# SolarPanels_Power_Processing.net
KiCad netlist of a schematic drawn in EAGLE
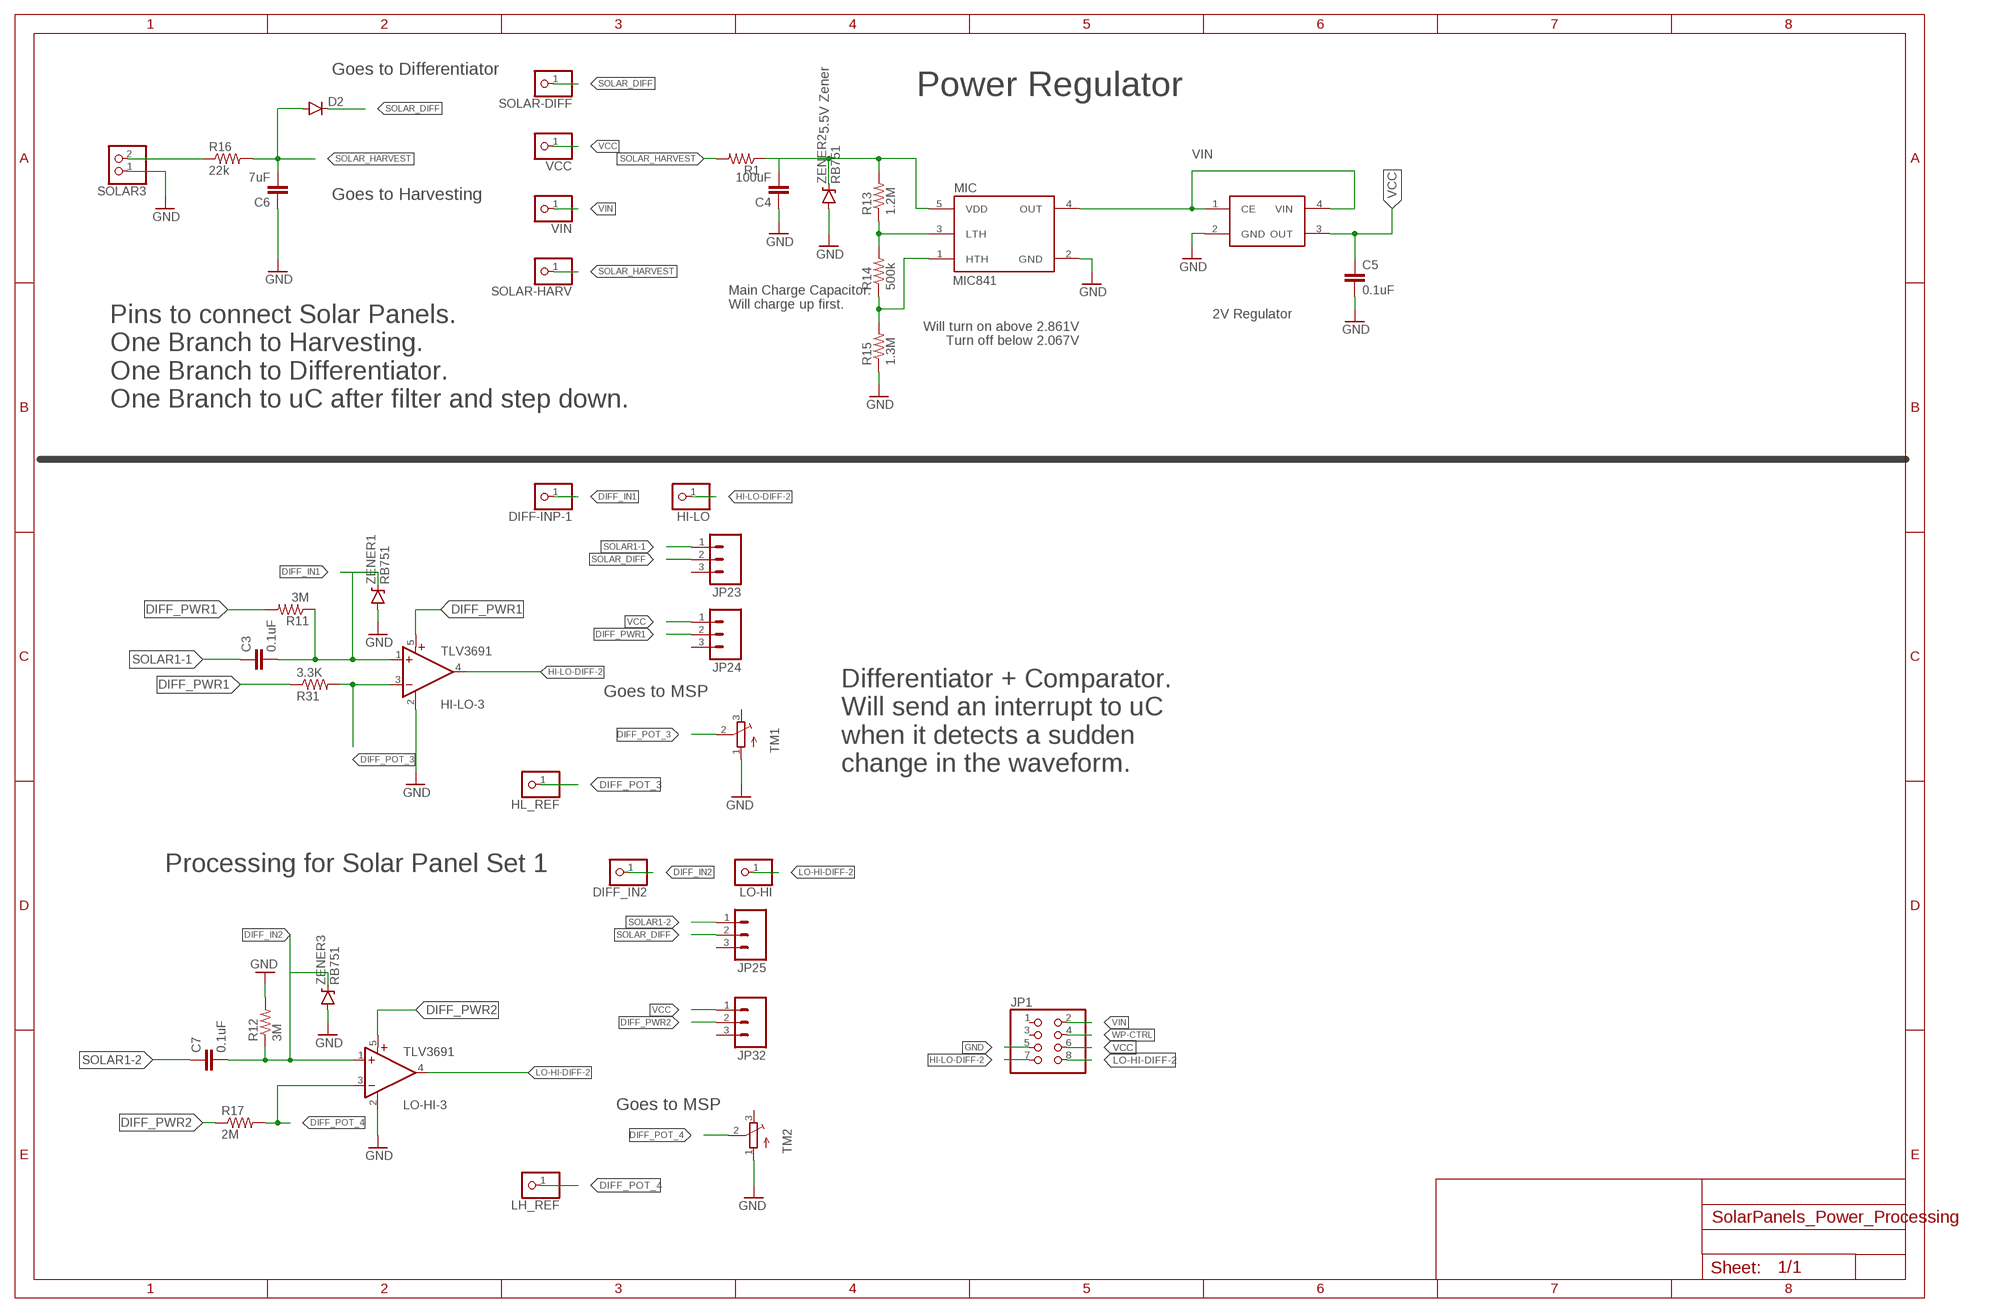
[diagram p0: schematic, sheet 1]

(export (version "E")
  (design (tool "Eeschema 10.0.6"))
  (components
    (comp (ref "3.3K")
      (value "R31")
      (footprint "eagle-import:0805")
      (libsource (lib "eagle-import") (part "RESISTOR0805-RES"))
    )
    (comp (ref "C3")
      (value "0.1uF")
      (footprint "eagle-import:0805")
      (libsource (lib "eagle-import") (part "CAP0805"))
    )
    (comp (ref "C4")
      (value "100uF")
      (footprint "eagle-import:0805")
      (libsource (lib "eagle-import") (part "CAP0805"))
    )
    (comp (ref "C5")
      (value "0.1uF")
      (footprint "eagle-import:0805")
      (libsource (lib "eagle-import") (part "CAP0805"))
    )
    (comp (ref "C6")
      (value "7uF")
      (footprint "eagle-import:0805")
      (libsource (lib "eagle-import") (part "CAP0805"))
    )
    (comp (ref "C7")
      (value "0.1uF")
      (footprint "eagle-import:0805")
      (libsource (lib "eagle-import") (part "CAP0805"))
    )
    (comp (ref "D2")
      (value "DIODESOD523")
      (footprint "eagle-import:SOD523")
      (libsource (lib "eagle-import") (part "DIODESOD523"))
    )
    (comp (ref "DIFF-INP-1")
      (value "PINHD-1X1")
      (footprint "eagle-import:1X01")
      (libsource (lib "eagle-import") (part "PINHD-1X1"))
    )
    (comp (ref "DIFF_IN2")
      (value "PINHD-1X1")
      (footprint "eagle-import:1X01")
      (libsource (lib "eagle-import") (part "PINHD-1X1"))
    )
    (comp (ref "HI-LO")
      (value "PINHD-1X1")
      (footprint "eagle-import:1X01")
      (libsource (lib "eagle-import") (part "PINHD-1X1"))
    )
    (comp (ref "HI-LO-3")
      (value "TLV3691")
      (footprint "eagle-import:SC70-5")
      (libsource (lib "eagle-import") (part "TLV3691"))
    )
    (comp (ref "HL_REF")
      (value "PINHD-1X1")
      (footprint "eagle-import:1X01")
      (libsource (lib "eagle-import") (part "PINHD-1X1"))
    )
    (comp (ref "JP1")
      (value "PINHD-2X4/90")
      (footprint "eagle-import:2X04_90")
      (libsource (lib "eagle-import") (part "PINHD-2X4/90"))
    )
    (comp (ref "JP23")
      (value "M03")
      (footprint "eagle-import:1X03-1.27MM")
      (libsource (lib "eagle-import") (part "M03"))
    )
    (comp (ref "JP24")
      (value "M03")
      (footprint "eagle-import:1X03-1.27MM")
      (libsource (lib "eagle-import") (part "M03"))
    )
    (comp (ref "JP25")
      (value "M03")
      (footprint "eagle-import:1X03-1.27MM")
      (libsource (lib "eagle-import") (part "M03"))
    )
    (comp (ref "JP32")
      (value "M03")
      (footprint "eagle-import:1X03-1.27MM")
      (libsource (lib "eagle-import") (part "M03"))
    )
    (comp (ref "LH_REF")
      (value "PINHD-1X1")
      (footprint "eagle-import:1X01")
      (libsource (lib "eagle-import") (part "PINHD-1X1"))
    )
    (comp (ref "LO-HI")
      (value "PINHD-1X1")
      (footprint "eagle-import:1X01")
      (libsource (lib "eagle-import") (part "PINHD-1X1"))
    )
    (comp (ref "LO-HI-3")
      (value "TLV3691")
      (footprint "eagle-import:SC70-5")
      (libsource (lib "eagle-import") (part "TLV3691"))
    )
    (comp (ref "MIC")
      (value "MIC841")
      (footprint "eagle-import:SC70-5")
      (libsource (lib "eagle-import") (part "MIC841"))
    )
    (comp (ref "NCP")
      (value "NCP583")
      (footprint "eagle-import:SC82-AB_1PRIMARY")
      (libsource (lib "eagle-import") (part "NCP583"))
    )
    (comp (ref "R1")
      (value "RESISTOR0805-RES")
      (footprint "eagle-import:0805")
      (libsource (lib "eagle-import") (part "RESISTOR0805-RES"))
    )
    (comp (ref "R11")
      (value "3M")
      (footprint "eagle-import:0805")
      (libsource (lib "eagle-import") (part "RESISTOR0805-RES"))
    )
    (comp (ref "R12")
      (value "3M")
      (footprint "eagle-import:0805")
      (libsource (lib "eagle-import") (part "RESISTOR0805-RES"))
    )
    (comp (ref "R13")
      (value "1.2M")
      (footprint "eagle-import:0805")
      (libsource (lib "eagle-import") (part "RESISTOR0805-RES"))
    )
    (comp (ref "R14")
      (value "500k")
      (footprint "eagle-import:0805")
      (libsource (lib "eagle-import") (part "RESISTOR0805-RES"))
    )
    (comp (ref "R15")
      (value "1.3M")
      (footprint "eagle-import:0805")
      (libsource (lib "eagle-import") (part "RESISTOR0805-RES"))
    )
    (comp (ref "R16")
      (value "22k")
      (footprint "eagle-import:0805")
      (libsource (lib "eagle-import") (part "RESISTOR0805-RES"))
    )
    (comp (ref "R17")
      (value "2M")
      (footprint "eagle-import:0805")
      (libsource (lib "eagle-import") (part "RESISTOR0805-RES"))
    )
    (comp (ref "SOLAR-DIFF")
      (value "PINHD-1X1")
      (footprint "eagle-import:1X01")
      (libsource (lib "eagle-import") (part "PINHD-1X1"))
    )
    (comp (ref "SOLAR-HARV")
      (value "PINHD-1X1")
      (footprint "eagle-import:1X01")
      (libsource (lib "eagle-import") (part "PINHD-1X1"))
    )
    (comp (ref "SOLAR3")
      (value "PINHD-1X2")
      (footprint "eagle-import:1X02")
      (libsource (lib "eagle-import") (part "PINHD-1X2"))
    )
    (comp (ref "TM1")
      (value "TRIMPOTTC33X")
      (footprint "eagle-import:TC33X")
      (libsource (lib "eagle-import") (part "TRIMPOTTC33X"))
    )
    (comp (ref "TM2")
      (value "TRIMPOTTC33X")
      (footprint "eagle-import:TC33X")
      (libsource (lib "eagle-import") (part "TRIMPOTTC33X"))
    )
    (comp (ref "VCC")
      (value "PINHD-1X1")
      (footprint "eagle-import:1X01")
      (libsource (lib "eagle-import") (part "PINHD-1X1"))
    )
    (comp (ref "VIN")
      (value "PINHD-1X1")
      (footprint "eagle-import:1X01")
      (libsource (lib "eagle-import") (part "PINHD-1X1"))
    )
    (comp (ref "ZENER1")
      (value "RB751")
      (footprint "eagle-import:SOD-523")
      (libsource (lib "eagle-import") (part "DIODE-ZENER"))
    )
    (comp (ref "ZENER2")
      (value "RB751")
      (footprint "eagle-import:SOD-523")
      (libsource (lib "eagle-import") (part "DIODE-ZENER"))
    )
    (comp (ref "ZENER3")
      (value "RB751")
      (footprint "eagle-import:SOD-523")
      (libsource (lib "eagle-import") (part "DIODE-ZENER"))
    )
  )
  (nets
    (net (code "1") (name "DIFF_IN1") (class "Default")
      (node (ref "C3") (pin "2") (pinfunction "2_2") (pintype "passive"))
      (node (ref "DIFF-INP-1") (pin "1") (pinfunction "1_1") (pintype "passive"))
      (node (ref "HI-LO-3") (pin "1") (pinfunction "+IN_1") (pintype "input"))
      (node (ref "R11") (pin "1") (pinfunction "1_1") (pintype "passive"))
      (node (ref "ZENER1") (pin "CATHODE") (pinfunction "C_CATHODE") (pintype "passive"))
    )
    (net (code "2") (name "DIFF_IN2") (class "Default")
      (node (ref "C7") (pin "2") (pinfunction "2_2") (pintype "passive"))
      (node (ref "DIFF_IN2") (pin "1") (pinfunction "1_1") (pintype "passive"))
      (node (ref "LO-HI-3") (pin "1") (pinfunction "+IN_1") (pintype "input"))
      (node (ref "R12") (pin "1") (pinfunction "1_1") (pintype "passive"))
      (node (ref "ZENER3") (pin "CATHODE") (pinfunction "C_CATHODE") (pintype "passive"))
    )
    (net (code "3") (name "DIFF_POT_3") (class "Default")
      (node (ref "3.3K") (pin "2") (pinfunction "2_2") (pintype "passive"))
      (node (ref "HI-LO-3") (pin "3") (pinfunction "-IN_3") (pintype "input"))
      (node (ref "HL_REF") (pin "1") (pinfunction "1_1") (pintype "passive"))
      (node (ref "TM1") (pin "2") (pinfunction "S_2") (pintype "passive"))
    )
    (net (code "4") (name "DIFF_POT_4") (class "Default")
      (node (ref "LH_REF") (pin "1") (pinfunction "1_1") (pintype "passive"))
      (node (ref "LO-HI-3") (pin "3") (pinfunction "-IN_3") (pintype "input"))
      (node (ref "R17") (pin "2") (pinfunction "2_2") (pintype "passive"))
      (node (ref "TM2") (pin "2") (pinfunction "S_2") (pintype "passive"))
    )
    (net (code "5") (name "DIFF_PWR1") (class "Default")
      (node (ref "3.3K") (pin "1") (pinfunction "1_1") (pintype "passive"))
      (node (ref "HI-LO-3") (pin "5") (pinfunction "V+_5") (pintype "power_in"))
      (node (ref "JP24") (pin "2") (pinfunction "2_2") (pintype "passive"))
      (node (ref "R11") (pin "2") (pinfunction "2_2") (pintype "passive"))
    )
    (net (code "6") (name "DIFF_PWR2") (class "Default")
      (node (ref "JP32") (pin "2") (pinfunction "2_2") (pintype "passive"))
      (node (ref "LO-HI-3") (pin "5") (pinfunction "V+_5") (pintype "power_in"))
      (node (ref "R17") (pin "1") (pinfunction "1_1") (pintype "passive"))
    )
    (net (code "7") (name "GND") (class "Default")
      (node (ref "C4") (pin "1") (pinfunction "1_1") (pintype "passive"))
      (node (ref "C5") (pin "2") (pinfunction "2_2") (pintype "passive"))
      (node (ref "C6") (pin "1") (pinfunction "1_1") (pintype "passive"))
      (node (ref "HI-LO-3") (pin "2") (pinfunction "GND_2") (pintype "power_in"))
      (node (ref "JP1") (pin "5") (pinfunction "5_5") (pintype "passive"))
      (node (ref "LO-HI-3") (pin "2") (pinfunction "GND_2") (pintype "power_in"))
      (node (ref "MIC") (pin "2") (pinfunction "GND_2") (pintype "bidirectional"))
      (node (ref "NCP") (pin "2") (pinfunction "GND_2") (pintype "bidirectional"))
      (node (ref "R12") (pin "2") (pinfunction "2_2") (pintype "passive"))
      (node (ref "R15") (pin "1") (pinfunction "1_1") (pintype "passive"))
      (node (ref "SOLAR3") (pin "1") (pinfunction "1_1") (pintype "passive"))
      (node (ref "TM1") (pin "1") (pinfunction "A_1") (pintype "passive"))
      (node (ref "TM2") (pin "1") (pinfunction "A_1") (pintype "passive"))
      (node (ref "ZENER1") (pin "ANODE") (pinfunction "A_ANODE") (pintype "passive"))
      (node (ref "ZENER2") (pin "ANODE") (pinfunction "A_ANODE") (pintype "passive"))
      (node (ref "ZENER3") (pin "ANODE") (pinfunction "A_ANODE") (pintype "passive"))
    )
    (net (code "8") (name "HI-LO-DIFF-2") (class "Default")
      (node (ref "HI-LO") (pin "1") (pinfunction "1_1") (pintype "passive"))
      (node (ref "HI-LO-3") (pin "4") (pinfunction "OUT_4") (pintype "output"))
      (node (ref "JP1") (pin "7") (pinfunction "7_7") (pintype "passive"))
    )
    (net (code "9") (name "LO-HI-DIFF-2") (class "Default")
      (node (ref "JP1") (pin "8") (pinfunction "8_8") (pintype "passive"))
      (node (ref "LO-HI") (pin "1") (pinfunction "1_1") (pintype "passive"))
      (node (ref "LO-HI-3") (pin "4") (pinfunction "OUT_4") (pintype "output"))
    )
    (net (code "10") (name "Net-(MIC-HTH)") (class "Default")
      (node (ref "MIC") (pin "1") (pinfunction "HTH_1") (pintype "bidirectional"))
      (node (ref "R14") (pin "1") (pinfunction "1_1") (pintype "passive"))
      (node (ref "R15") (pin "2") (pinfunction "2_2") (pintype "passive"))
    )
    (net (code "11") (name "Net-(MIC-LTH)") (class "Default")
      (node (ref "MIC") (pin "3") (pinfunction "LTH_3") (pintype "bidirectional"))
      (node (ref "R13") (pin "1") (pinfunction "1_1") (pintype "passive"))
      (node (ref "R14") (pin "2") (pinfunction "2_2") (pintype "passive"))
    )
    (net (code "12") (name "Net-(MIC-VDD)") (class "Default")
      (node (ref "C4") (pin "2") (pinfunction "2_2") (pintype "passive"))
      (node (ref "MIC") (pin "5") (pinfunction "VDD_5") (pintype "bidirectional"))
      (node (ref "R1") (pin "1") (pinfunction "1_1") (pintype "passive"))
      (node (ref "R13") (pin "2") (pinfunction "2_2") (pintype "passive"))
      (node (ref "ZENER2") (pin "CATHODE") (pinfunction "C_CATHODE") (pintype "passive"))
    )
    (net (code "13") (name "Net-(R16-Pad1)") (class "Default")
      (node (ref "R16") (pin "1") (pinfunction "1_1") (pintype "passive"))
      (node (ref "SOLAR3") (pin "2") (pinfunction "2_2") (pintype "passive"))
    )
    (net (code "14") (name "SOLAR1-1") (class "Default")
      (node (ref "C3") (pin "1") (pinfunction "1_1") (pintype "passive"))
      (node (ref "JP23") (pin "1") (pinfunction "1_1") (pintype "passive"))
    )
    (net (code "15") (name "SOLAR1-2") (class "Default")
      (node (ref "C7") (pin "1") (pinfunction "1_1") (pintype "passive"))
      (node (ref "JP25") (pin "1") (pinfunction "1_1") (pintype "passive"))
    )
    (net (code "16") (name "SOLAR_DIFF") (class "Default")
      (node (ref "D2") (pin "C") (pinfunction "C_C") (pintype "passive"))
      (node (ref "JP23") (pin "2") (pinfunction "2_2") (pintype "passive"))
      (node (ref "JP25") (pin "2") (pinfunction "2_2") (pintype "passive"))
      (node (ref "SOLAR-DIFF") (pin "1") (pinfunction "1_1") (pintype "passive"))
    )
    (net (code "17") (name "SOLAR_HARVEST") (class "Default")
      (node (ref "C6") (pin "2") (pinfunction "2_2") (pintype "passive"))
      (node (ref "D2") (pin "A") (pinfunction "A_A") (pintype "passive"))
      (node (ref "R1") (pin "2") (pinfunction "2_2") (pintype "passive"))
      (node (ref "R16") (pin "2") (pinfunction "2_2") (pintype "passive"))
      (node (ref "SOLAR-HARV") (pin "1") (pinfunction "1_1") (pintype "passive"))
    )
    (net (code "18") (name "VCC") (class "Default")
      (node (ref "C5") (pin "1") (pinfunction "1_1") (pintype "passive"))
      (node (ref "JP1") (pin "6") (pinfunction "6_6") (pintype "passive"))
      (node (ref "JP24") (pin "1") (pinfunction "1_1") (pintype "passive"))
      (node (ref "JP32") (pin "1") (pinfunction "1_1") (pintype "passive"))
      (node (ref "NCP") (pin "3") (pinfunction "OUT_3") (pintype "bidirectional"))
      (node (ref "VCC") (pin "1") (pinfunction "1_1") (pintype "passive"))
    )
    (net (code "19") (name "VIN") (class "Default")
      (node (ref "JP1") (pin "2") (pinfunction "2_2") (pintype "passive"))
      (node (ref "MIC") (pin "4") (pinfunction "OUT_4") (pintype "bidirectional"))
      (node (ref "NCP") (pin "1") (pinfunction "CE_1") (pintype "bidirectional"))
      (node (ref "NCP") (pin "4") (pinfunction "VIN_4") (pintype "bidirectional"))
      (node (ref "VIN") (pin "1") (pinfunction "1_1") (pintype "passive"))
    )
    (net (code "20") (name "WP-CTRL") (class "Default")
      (node (ref "JP1") (pin "4") (pinfunction "4_4") (pintype "passive"))
    )
    (net (code "21") (name "unconnected-(JP1-Pad1)") (class "Default")
      (node (ref "JP1") (pin "1") (pinfunction "1_1") (pintype "passive"))
    )
    (net (code "22") (name "unconnected-(JP1-Pad3)") (class "Default")
      (node (ref "JP1") (pin "3") (pinfunction "3_3") (pintype "passive"))
    )
    (net (code "23") (name "unconnected-(JP23-Pad3)") (class "Default")
      (node (ref "JP23") (pin "3") (pinfunction "3_3") (pintype "passive"))
    )
    (net (code "24") (name "unconnected-(JP24-Pad3)") (class "Default")
      (node (ref "JP24") (pin "3") (pinfunction "3_3") (pintype "passive"))
    )
    (net (code "25") (name "unconnected-(JP25-Pad3)") (class "Default")
      (node (ref "JP25") (pin "3") (pinfunction "3_3") (pintype "passive"))
    )
    (net (code "26") (name "unconnected-(JP32-Pad3)") (class "Default")
      (node (ref "JP32") (pin "3") (pinfunction "3_3") (pintype "passive"))
    )
    (net (code "27") (name "unconnected-(TM1-E-Pad3)") (class "Default")
      (node (ref "TM1") (pin "3") (pinfunction "E_3") (pintype "passive"))
    )
    (net (code "28") (name "unconnected-(TM2-E-Pad3)") (class "Default")
      (node (ref "TM2") (pin "3") (pinfunction "E_3") (pintype "passive"))
    )
  )
)
